# Motor_Interface_-_Pre-Charge_HV.net
KiCad netlist of a schematic drawn in Altium Designer
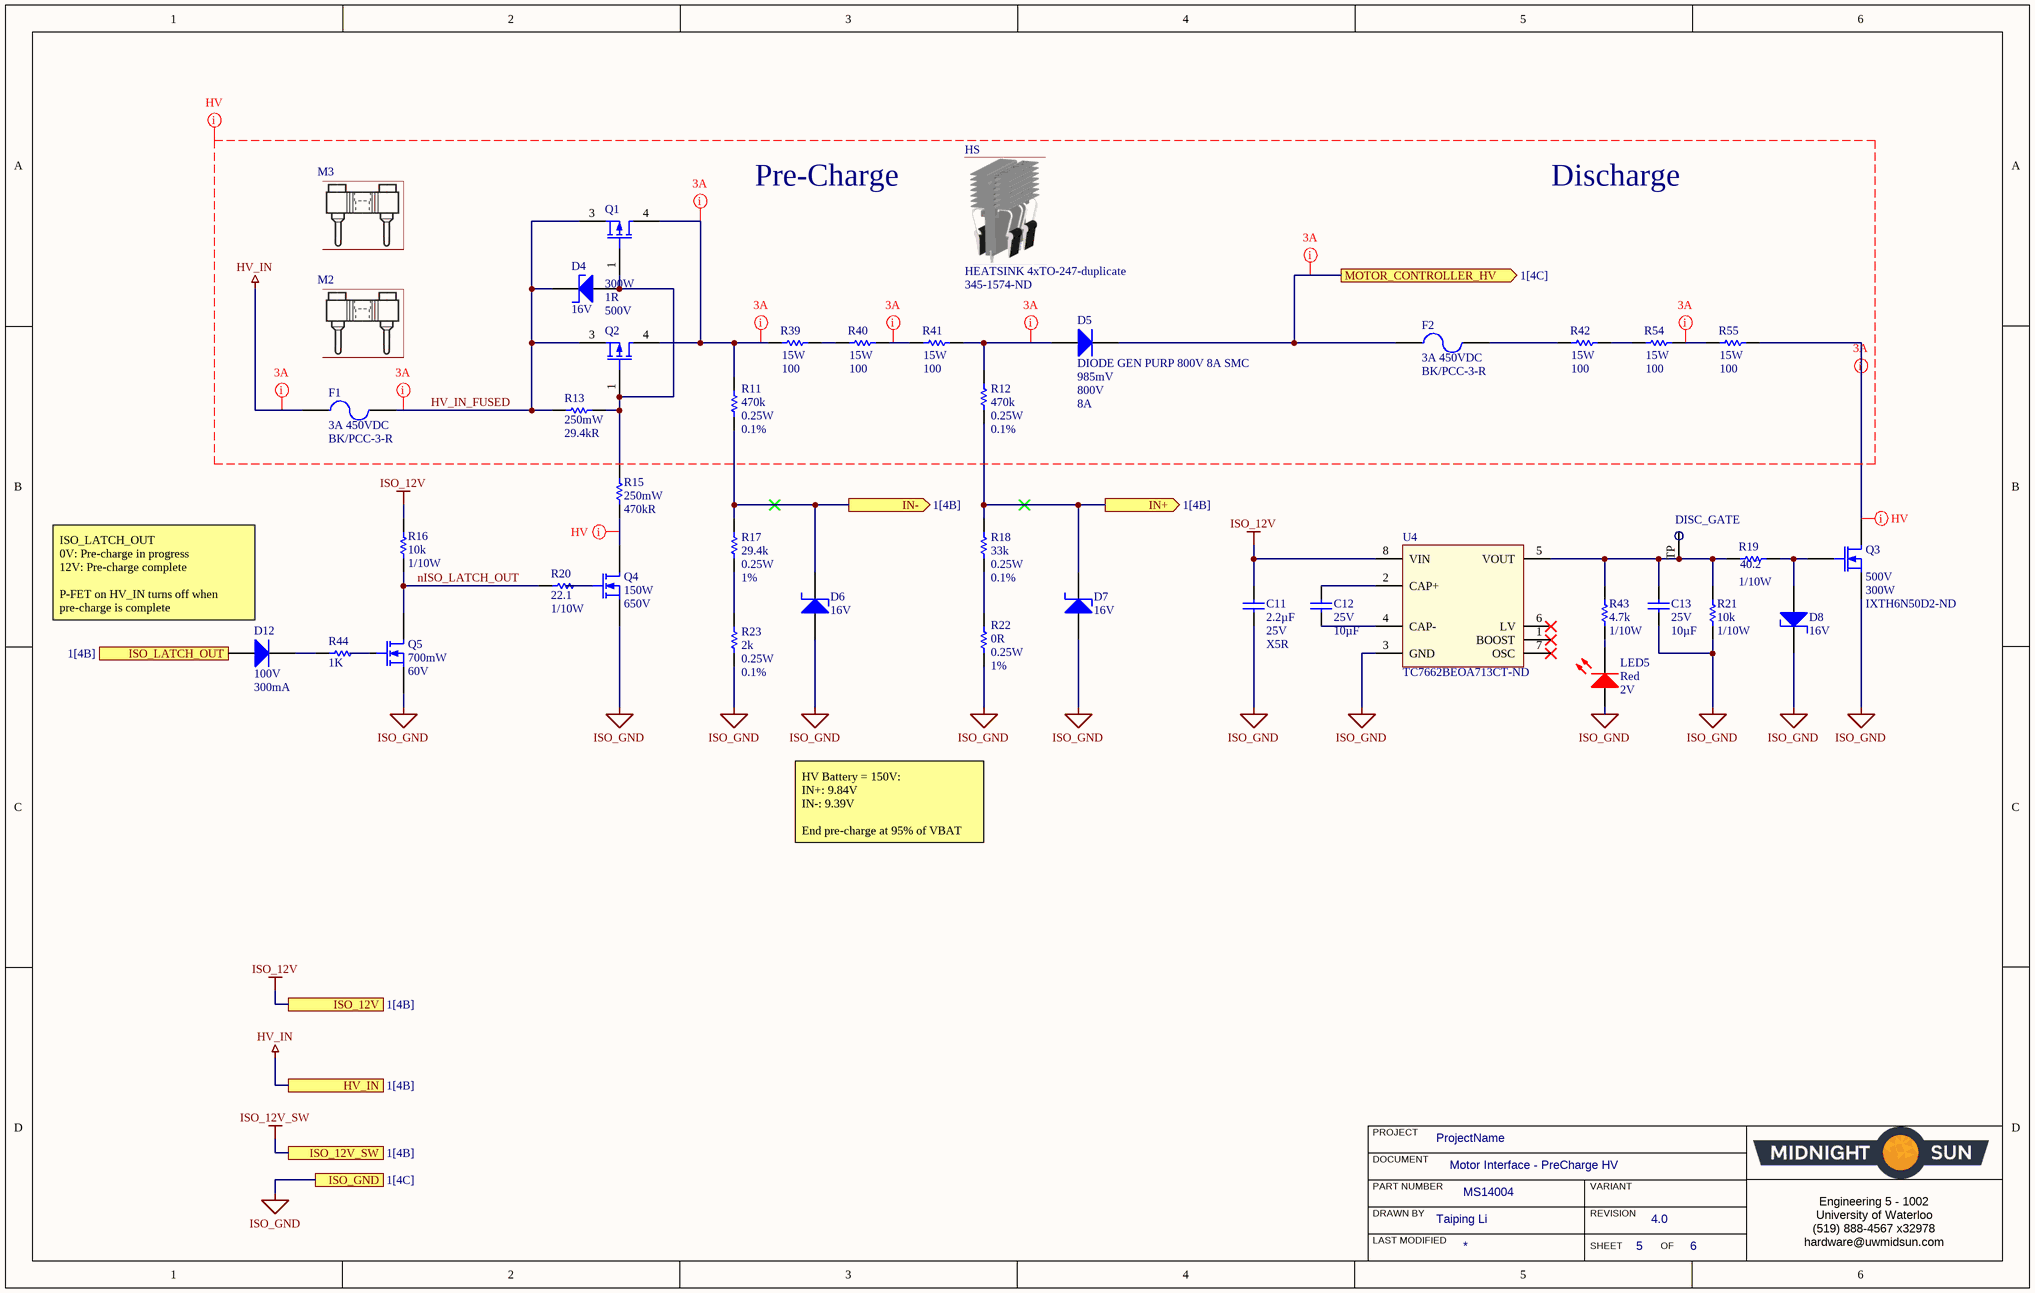
[diagram p0: Motor Interface - Pre-Charge HV.SchDoc]

(export (version "E")
  (design (tool "Eeschema 10.0.6"))
  (components
    (comp (ref "C11")
      (value "CAP CER 2.2UF 25V 10% X5R 0603")
      (footprint "CAP, 0603")
      (description "2.2µF ±10% 25V Ceramic Capacitor X5R 0603 (1608 Metric)")
      (fields
        (field (name "TOLERANCE") "±10%")
        (field (name "CAPACITANCE") "2.2µF")
        (field (name "VOLTAGE") "25V")
        (field (name "TEMPERATURE COEFFICIENT") "X5R")
      )
      (libsource (lib "Schematic Diagrams") (part "CAP CER 2.2UF 25V 10% X5R 0603"))
    )
    (comp (ref "C12")
      (value "CAP CER 10uF 25V 10% X5R 0805")
      (footprint "CAP, 0805")
      (description "10µF ±10% 25V Ceramic Capacitor X5R 0805 (2012 Metric)")
      (fields
        (field (name "MANUFACTURER") "Murata Electronics North America")
        (field (name "MANUFACTURER PART NUMBER") "GRM21BR61E106KA73L")
        (field (name "VOLTAGE - RATED") "25V")
        (field (name "CAPACITANCE") "10µF")
      )
      (libsource (lib "Schematic Diagrams") (part "CAP CER 10uF 25V 10% X5R 0805"))
    )
    (comp (ref "C13")
      (value "CAP CER 10uF 25V 10% X5R 0805")
      (footprint "CAP, 0805")
      (description "10µF ±10% 25V Ceramic Capacitor X5R 0805 (2012 Metric)")
      (fields
        (field (name "MANUFACTURER") "Murata Electronics North America")
        (field (name "MANUFACTURER PART NUMBER") "GRM21BR61E106KA73L")
        (field (name "VOLTAGE - RATED") "25V")
        (field (name "CAPACITANCE") "10µF")
      )
      (libsource (lib "Schematic Diagrams") (part "CAP CER 10uF 25V 10% X5R 0805"))
    )
    (comp (ref "D4")
      (value "DIODE ZENER 16V 5W DO-214AA (SMB)")
      (footprint "DO-214AA Diode")
      (description "Zener Diode 16V 5W ±5% Surface Mount DO-214AA (SMB)")
      (fields
        (field (name "MANUFACTURE PART NUMBER") "SMBJ5353B-TP")
        (field (name "VOLTAGE - ZENER (NOM)") "16V")
      )
      (libsource (lib "Schematic Diagrams") (part "DIODE ZENER 16V 5W DO-214AA (SMB)"))
    )
    (comp (ref "D5")
      (value "DIODE GEN PURP 800V 8A SMC")
      (footprint "DIODE, SMC")
      (fields
        (field (name "MANUFACTURER") "Diodes")
        (field (name "MANUFACTURER PART NUMBER") "S8KC-13")
        (field (name "FORWARD VOLTAGE") "985mV")
        (field (name "MAX REVERSE VOLTAGE (DC)") "800V")
        (field (name "FORWARD CURRENT") "8A")
      )
      (libsource (lib "Schematic Diagrams") (part "DIODE GEN PURP 800V 8A SMC"))
    )
    (comp (ref "D6")
      (value "DIODE ZENER 16V 5W DO-214AA (SMB)")
      (footprint "DO-214AA Diode")
      (description "Zener Diode 16V 5W ±5% Surface Mount DO-214AA (SMB)")
      (fields
        (field (name "MANUFACTURE PART NUMBER") "SMBJ5353B-TP")
        (field (name "VOLTAGE - ZENER (NOM)") "16V")
      )
      (libsource (lib "Schematic Diagrams") (part "DIODE ZENER 16V 5W DO-214AA (SMB)"))
    )
    (comp (ref "D7")
      (value "DIODE ZENER 16V 5W DO-214AA (SMB)")
      (footprint "DO-214AA Diode")
      (description "Zener Diode 16V 5W ±5% Surface Mount DO-214AA (SMB)")
      (fields
        (field (name "MANUFACTURE PART NUMBER") "SMBJ5353B-TP")
        (field (name "VOLTAGE - ZENER (NOM)") "16V")
      )
      (libsource (lib "Schematic Diagrams") (part "DIODE ZENER 16V 5W DO-214AA (SMB)"))
    )
    (comp (ref "D8")
      (value "DIODE ZENER 16V 5W DO-214AA (SMB)")
      (footprint "DO-214AA Diode")
      (description "Zener Diode 16V 5W ±5% Surface Mount DO-214AA (SMB)")
      (fields
        (field (name "MANUFACTURE PART NUMBER") "SMBJ5353B-TP")
        (field (name "VOLTAGE - ZENER (NOM)") "16V")
      )
      (libsource (lib "Schematic Diagrams") (part "DIODE ZENER 16V 5W DO-214AA (SMB)"))
    )
    (comp (ref "D12")
      (value "DIODE GEN PURP 100V 300MA SOD123")
      (footprint "DIODE GEN PURP 100V 300MA SOD123")
      (description "Diode Standard 100V 300mA (DC) Surface Mount SOD-123")
      (fields
        (field (name "MANUFACTURER") "Diodes Zetex")
        (field (name "MANUFACTURER PART NUMBER") "1N4148WQ-7-F")
        (field (name "MAX REPETITIVE REVERSE VOLTAGE (VRRM)") "100V")
        (field (name "FORWARD CURRENT") "300mA")
      )
      (libsource (lib "Schematic Diagrams") (part "DIODE GEN PURP 100V 300MA SOD123"))
    )
    (comp (ref "DISC_GATE")
      (value "Test Point")
      (footprint "Test Point")
      (libsource (lib "Schematic Diagrams") (part "Test Point"))
    )
    (comp (ref "F1")
      (value "3A 450VDC")
      (footprint "FUSE 5A 400VDC RADIAL")
      (description "FUSE BOARD MNT 3A 250VAC/450VDC")
      (fields (field (name "MANUFACTURER") "Eaton") (field (name "MANUFACTURER PART NUMBER") "BK/PCC-3-R"))
      (libsource (lib "Schematic Diagrams") (part "FUSE 3A 250VAC/450VDC RADIAL"))
    )
    (comp (ref "F2")
      (value "3A 450VDC")
      (footprint "FUSE 5A 400VDC RADIAL")
      (description "FUSE BOARD MNT 3A 250VAC/450VDC")
      (fields (field (name "MANUFACTURER") "Eaton") (field (name "MANUFACTURER PART NUMBER") "BK/PCC-3-R"))
      (libsource (lib "Schematic Diagrams") (part "FUSE 3A 250VAC/450VDC RADIAL"))
    )
    (comp (ref "HS")
      (value "HEATSINK 4xTO-247-duplicate")
      (footprint "HEATSINK 4x TO-247 - duplicate")
      (description "n Heat Sink TO-220, TO-247, TO-264 Aluminum Board Level, Vertical")
      (fields
        (field (name "MANUFACTURER") "Wakefield")
        (field (name "MANUFACTURER PART NUMBER") "OMNI-UNI-30-50-D")
        (field (name "SUPPLIER PART NUMBER 1") "345-1574-ND")
      )
      (libsource (lib "Schematic Diagrams") (part "HEATSINK 4xTO-247-duplicate"))
    )
    (comp (ref "LED5")
      (value "LED RED CLEAR 2V 0603")
      (footprint "LED_0603")
      (description "Red 631nm LED Indication - Discrete 2V 0603 (1608 Metric)")
      (fields
        (field (name "MANUFACTURER") "Wurth Electronics Inc.")
        (field (name "MANUFACTURER PART NUMBER") "150060RS75000")
        (field (name "COLOR") "Red")
        (field (name "VOLTAGE - FORWARD (VF) (TYP)") "2V")
      )
      (libsource (lib "Schematic Diagrams") (part "LED RED CLEAR 2V 0603"))
    )
    (comp (ref "M2")
      (value "FUSE HOLDER PC-TRON RADIAL")
      (description "Fuse Holder 1 Circuit Radial PCB")
      (fields (field (name "MANUFACTURER") "Eaton") (field (name "MANUFACTURER PART NUMBER") "BK/PCS"))
      (libsource (lib "Schematic Diagrams") (part "FUSE HOLDER PC-TRON RADIAL"))
    )
    (comp (ref "M3")
      (value "FUSE HOLDER PC-TRON RADIAL")
      (description "Fuse Holder 1 Circuit Radial PCB")
      (fields (field (name "MANUFACTURER") "Eaton") (field (name "MANUFACTURER PART NUMBER") "BK/PCS"))
      (libsource (lib "Schematic Diagrams") (part "FUSE HOLDER PC-TRON RADIAL"))
    )
    (comp (ref "Q1")
      (value "IXTA10P50P")
      (footprint "P-CH MOSFET 500V 10A 300W TO-263")
      (description "P-Channel 500V 10A (Tc) 300W (Tc) Surface Mount TO-263 (IXTA)")
      (fields
        (field (name "MANUFACTURER") "IXYS")
        (field (name "MAX POWER DISSIPATION") "300W")
        (field (name "RDS ON MAX") "1R")
        (field (name "DRAIN TO SOURCE VOLTAGE (VDSS)") "500V")
      )
      (libsource (lib "Schematic Diagrams") (part "MOSFET P-CH 500V 10A 300W TO-263"))
    )
    (comp (ref "Q2")
      (value "IXTA10P50P")
      (footprint "P-CH MOSFET 500V 10A 300W TO-263")
      (description "P-Channel 500V 10A (Tc) 300W (Tc) Surface Mount TO-263 (IXTA)")
      (fields (field (name "MANUFACTURER") "IXYS"))
      (libsource (lib "Schematic Diagrams") (part "MOSFET P-CH 500V 10A 300W TO-263"))
    )
    (comp (ref "Q3")
      (value "MOSFET DEPLETION N-CH 500V 6A TO247")
      (footprint "N-CH Depletion Mode TO-247-3")
      (description "N-Channel 500V 6A (Tc) 300W (Tc) Through Hole TO-247 (IXTH)")
      (fields
        (field (name "MANUFACTURER") "IXYS")
        (field (name "MANUFACTURER PART NUMBER") "IXTH6N50D2")
        (field (name "DRAIN TO SOURCE VOLTAGE (VDSS)") "500V")
        (field (name "MAX POWER DISSIPATION") "300W")
        (field (name "SUPPLIER PART NUMBER 1") "IXTH6N50D2-ND")
      )
      (libsource (lib "Schematic Diagrams") (part "MOSFET DEPLETION N-CH 500V 6A TO247"))
    )
    (comp (ref "Q4")
      (value "MOSFET N-CH 650V 8A X2 TO-263")
      (footprint "P-CH MOSFET 500V 10A 300W TO-263")
      (description "N-Channel 650V 8A (Tc) 150W (Tc) Surface Mount TO-263")
      (fields
        (field (name "MANUFACTURER") "IXYS")
        (field (name "MAX POWER DISSIPATION") "150W")
        (field (name "DRAIN TO SOURCE VOLTAGE (VDSS)") "650V")
        (field (name "MANUFACTURER PART NUMBER") "IXTA8N65X2")
      )
      (libsource (lib "Schematic Diagrams") (part "MOSFET N-CH 650V 8A X2 TO-263"))
    )
    (comp (ref "Q5")
      (value "MOSFET N-CH 60V 310MA SOT23")
      (footprint "SOT23")
      (description "N-Channel 60V 310mA (Ta) 370mW (Ta) Surface Mount SOT-23")
      (fields
        (field (name "MANUFACTURER") "Diodes")
        (field (name "MANUFACTURER PART NUMBER") "DMN6140L-7")
        (field (name "MAX POWER DISSIPATION") "700mW")
        (field (name "DRAIN TO SOURCE VOLTAGE (VDSS)") "60V")
      )
      (libsource (lib "Schematic Diagrams") (part "MOSFET N-CH 60V 310MA SOT23"))
    )
    (comp (ref "R11")
      (value "RESISTOR")
      (footprint "RES 1206")
      (fields
        (field (name "MANUFACTURER") "Susumu")
        (field (name "MANUFACTURER PART NUMBER") "RG3216P-4703-B-T1")
        (field (name "TOLERANCE") "0.1%")
        (field (name "MAX POWER DISSIPATION") "0.25W")
        (field (name "RESISTANCE") "470k")
      )
      (libsource (lib "Schematic Diagrams") (part "RES SMD 470K OHM 0.1% 1/4W 1206"))
    )
    (comp (ref "R12")
      (value "RESISTOR")
      (footprint "RES 1206")
      (fields
        (field (name "MANUFACTURER") "Susumu")
        (field (name "MANUFACTURER PART NUMBER") "RG3216P-4703-B-T1")
        (field (name "TOLERANCE") "0.1%")
        (field (name "MAX POWER DISSIPATION") "0.25W")
        (field (name "RESISTANCE") "470k")
      )
      (libsource (lib "Schematic Diagrams") (part "RES SMD 470K OHM 0.1% 1/4W 1206"))
    )
    (comp (ref "R13")
      (value "Resistor")
      (footprint "RES 1206")
      (description "29.4 kOhms ±1% 0.25W, 1/4W Chip Resistor 1206 (3216 Metric) Automotive AEC-Q200 Thick Film")
      (fields
        (field (name "MANUFACTURER") "Panasonic")
        (field (name "MANUFACTURER PART NUMBER") "ERJ-8ENF2942V")
        (field (name "MAX POWER DISSIPATION") "250mW")
        (field (name "RESISTANCE") "29.4kR")
      )
      (libsource (lib "Schematic Diagrams") (part "RES SMD 29.4K OHM 1% 1/4W 1206"))
    )
    (comp (ref "R15")
      (value "RESISTOR")
      (footprint "RES 1206")
      (fields
        (field (name "MANUFACTURER") "Susumu")
        (field (name "MANUFACTURER PART NUMBER") "RG3216P-4703-B-T1")
        (field (name "TOLERANCE") "0.1%")
        (field (name "MAX POWER DISSIPATION") "250mW")
        (field (name "RESISTANCE") "470kR")
      )
      (libsource (lib "Schematic Diagrams") (part "RES SMD 470K OHM 0.1% 1/4W 1206"))
    )
    (comp (ref "R16")
      (value "RES 10K OHM 1% 1/10W 0603")
      (footprint "RES, 0603")
      (description "RES SMD 10K OHM 1% 1/10W 0603")
      (fields
        (field (name "TOLERANCE") "±1%")
        (field (name "RESISTANCE") "10k")
        (field (name "POWER") "1/10W")
      )
      (libsource (lib "Schematic Diagrams") (part "RES 10K OHM 1% 1/10W 0603"))
    )
    (comp (ref "R17")
      (value "Resistor")
      (footprint "RES 1206")
      (description "29.4 kOhms ±1% 0.25W, 1/4W Chip Resistor 1206 (3216 Metric) Automotive AEC-Q200 Thick Film")
      (fields
        (field (name "MANUFACTURER") "Panasonic")
        (field (name "MANUFACTURER PART NUMBER") "ERJ-8ENF2942V")
        (field (name "TOLERANCE") "1%")
        (field (name "MAX POWER DISSIPATION") "0.25W")
        (field (name "RESISTANCE") "29.4k")
      )
      (libsource (lib "Schematic Diagrams") (part "RES SMD 29.4K OHM 1% 1/4W 1206"))
    )
    (comp (ref "R18")
      (value "Resistor")
      (footprint "RES 1206")
      (description "33 kOhms ±0.1% 0.25W, 1/4W Chip Resistor 1206 (3216 Metric) Thin Film")
      (fields
        (field (name "MANUFACTURER") "Yageo")
        (field (name "MANUFACTURER PART NUMBER") "RT1206BRD0733KL")
        (field (name "TOLERANCE") "0.1%")
        (field (name "RESISTANCE") "33k")
        (field (name "MAX POWER DISSIPATION") "0.25W")
      )
      (libsource (lib "Schematic Diagrams") (part "RES SMD 33K OHM 0.1% 1/4W 1206"))
    )
    (comp (ref "R19")
      (value "RES 40.2 OHM 0.5% 1/10W 0603")
      (footprint "RES, 0603")
      (description "RES SMD 40.2 OHM 0.5% 1/10W 0603")
      (fields
        (field (name "TOLERANCE") "±0.5%")
        (field (name "RESISTANCE") "40.2")
        (field (name "POWER") "1/10W")
      )
      (libsource (lib "Schematic Diagrams") (part "RES 40.2 OHM 0.5% 1/10W 0603"))
    )
    (comp (ref "R20")
      (value "RES 22.1 OHM 1% 1/10W 0603")
      (footprint "RES, 0603")
      (description "22.1 Ohm ±1% 0.1W, 1/10W Chip Resistor 0603 (1608 Metric) Moisture Resistant Thick Film")
      (fields
        (field (name "TOLERANCE") "±1%")
        (field (name "RESISTANCE") "22.1")
        (field (name "POWER") "1/10W")
      )
      (libsource (lib "Schematic Diagrams") (part "RES 22.1 OHM 1% 1/10W 0603"))
    )
    (comp (ref "R21")
      (value "RES 10K OHM 1% 1/10W 0603")
      (footprint "RES, 0603")
      (description "RES SMD 10K OHM 1% 1/10W 0603")
      (fields
        (field (name "TOLERANCE") "±1%")
        (field (name "RESISTANCE") "10k")
        (field (name "POWER") "1/10W")
      )
      (libsource (lib "Schematic Diagrams") (part "RES 10K OHM 1% 1/10W 0603"))
    )
    (comp (ref "R22")
      (value "RES SMD 0 OHM JUMPER 1/4W 1206")
      (footprint "RES 1206")
      (description "0 Ohms Jumper 0.25W, 1/4W Chip Resistor 1206 (3216 Metric) Automotive AEC-Q200 Thick Film")
      (fields
        (field (name "MANUFACTURER") "Vishay")
        (field (name "MANUFACTURER PART NUMBER") "CRCW12060000Z0EA")
        (field (name "TOLERANCE") "1%")
        (field (name "POWER RATING") "0.25W")
        (field (name "RESISTANCE") "0R")
      )
      (libsource (lib "Schematic Diagrams") (part "RES SMD 0 OHM JUMPER 1/4W 1206"))
    )
    (comp (ref "R23")
      (value "RES SMD 2K OHM 0.1% 1/4W 1206")
      (footprint "RES 1206")
      (description "2 kOhms ±0.1% 0.25W, 1/4W Chip Resistor 1206 (3216 Metric) Automotive AEC-Q200 Thin Film")
      (fields
        (field (name "MANUFACTURER") "Panasonic")
        (field (name "MANUFACTURER PART NUMBER") "ERA-8AEB202V")
        (field (name "TOLERANCE") "0.1%")
        (field (name "MAX POWER DISSIPATION") "0.25W")
        (field (name "RESISTANCE") "2k")
      )
      (libsource (lib "Schematic Diagrams") (part "RES SMD 2K OHM 0.1% 1/4W 1206"))
    )
    (comp (ref "R39")
      (value "RES 100 OHM 15W 1% TO126")
      (footprint "RES TO-126-2")
      (description "100 Ohms ±1% 15W Through Hole Resistor TO-126-2 Moisture Resistant, Non-Inductive Thick Film")
      (fields (field (name "TOLERANCE") "1%"))
      (libsource (lib "Schematic Diagrams") (part "RES 100 OHM 15W 1% TO126"))
    )
    (comp (ref "R40")
      (value "RES 100 OHM 15W 1% TO126")
      (footprint "RES TO-126-2")
      (description "100 Ohms ±1% 15W Through Hole Resistor TO-126-2 Moisture Resistant, Non-Inductive Thick Film")
      (fields (field (name "TOLERANCE") "1%"))
      (libsource (lib "Schematic Diagrams") (part "RES 100 OHM 15W 1% TO126"))
    )
    (comp (ref "R41")
      (value "RES 100 OHM 15W 1% TO126")
      (footprint "RES TO-126-2")
      (description "100 Ohms ±1% 15W Through Hole Resistor TO-126-2 Moisture Resistant, Non-Inductive Thick Film")
      (fields (field (name "TOLERANCE") "1%"))
      (libsource (lib "Schematic Diagrams") (part "RES 100 OHM 15W 1% TO126"))
    )
    (comp (ref "R42")
      (value "RES 100 OHM 15W 1% TO126")
      (footprint "RES TO-126-2")
      (description "100 Ohms ±1% 15W Through Hole Resistor TO-126-2 Moisture Resistant, Non-Inductive Thick Film")
      (fields (field (name "TOLERANCE") "1%"))
      (libsource (lib "Schematic Diagrams") (part "RES 100 OHM 15W 1% TO126"))
    )
    (comp (ref "R43")
      (value "RES 4.7K OHM 1% 1/10W 0603")
      (footprint "RES, 0603")
      (description "4.7k Ohm ±1% 0.1W, 1/10W Chip Resistor 0603 (1608 Metric) Moisture Resistant Thick Film")
      (fields
        (field (name "TOLERANCE") "±1%")
        (field (name "RESISTANCE (OHMS)") "4.7k")
        (field (name "POWER (WATTS)") "1/10W")
      )
      (libsource (lib "Schematic Diagrams") (part "RES 4.7K OHM 1% 1/10W 0603"))
    )
    (comp (ref "R44")
      (value "1K")
      (footprint "RES, 0603")
      (description "1k Ohm ±5% 0.1W, 1/10W Chip Resistor 0603 (1608 Metric)")
      (fields
        (field (name "MANUFACTURER") "Yageo")
        (field (name "MANUFACTURER PART NUMBER") "RC0603JR-071KL")
      )
      (libsource (lib "Schematic Diagrams") (part "RES 1K OHM 5% 1/10W 0603"))
    )
    (comp (ref "R54")
      (value "RES 100 OHM 15W 1% TO126")
      (footprint "RES TO-126-2")
      (description "100 Ohms ±1% 15W Through Hole Resistor TO-126-2 Moisture Resistant, Non-Inductive Thick Film")
      (fields (field (name "TOLERANCE") "1%"))
      (libsource (lib "Schematic Diagrams") (part "RES 100 OHM 15W 1% TO126"))
    )
    (comp (ref "R55")
      (value "RES 100 OHM 15W 1% TO126")
      (footprint "RES TO-126-2")
      (description "100 Ohms ±1% 15W Through Hole Resistor TO-126-2 Moisture Resistant, Non-Inductive Thick Film")
      (fields (field (name "TOLERANCE") "1%"))
      (libsource (lib "Schematic Diagrams") (part "RES 100 OHM 15W 1% TO126"))
    )
    (comp (ref "U4")
      (value "IC REG SWTCHD CAP INV 20MA 8SOIC")
      (footprint "SOIC8")
      (fields
        (field (name "MANUFACTURER") "Microchip")
        (field (name "MANUFACTURER PART NUMBER") "TC7662BEOA713")
        (field (name "SUPPLIER PART NUMBER 1") "TC7662BEOA713CT-ND")
      )
      (libsource (lib "Schematic Diagrams") (part "IC REG SWTCHD CAP INV 20MA 8SOIC"))
    )
  )
  (nets
    (net (code "1") (name "/HV_IN_FUSED") (class "Default")
      (node (ref "D4") (pin "2") (pinfunction "K_2") (pintype "passive"))
      (node (ref "F1") (pin "2") (pinfunction "2_2") (pintype "passive"))
      (node (ref "Q1") (pin "3") (pinfunction "S_3") (pintype "passive"))
      (node (ref "Q2") (pin "3") (pinfunction "S_3") (pintype "passive"))
      (node (ref "R13") (pin "1") (pinfunction "1_1") (pintype "passive"))
    )
    (net (code "2") (name "/IN+") (class "Default")
      (node (ref "D7") (pin "2") (pinfunction "K_2") (pintype "passive"))
      (node (ref "R12") (pin "2") (pinfunction "2_2") (pintype "passive"))
      (node (ref "R18") (pin "1") (pinfunction "1_1") (pintype "passive"))
    )
    (net (code "3") (name "/IN-") (class "Default")
      (node (ref "D6") (pin "2") (pinfunction "K_2") (pintype "passive"))
      (node (ref "R11") (pin "2") (pinfunction "2_2") (pintype "passive"))
      (node (ref "R17") (pin "1") (pinfunction "1_1") (pintype "passive"))
    )
    (net (code "4") (name "/ISO_LATCH_OUT") (class "Default")
      (node (ref "D12") (pin "1") (pinfunction "A_1") (pintype "passive"))
    )
    (net (code "5") (name "/MOTOR_CONTROLLER_HV") (class "Default")
      (node (ref "D5") (pin "1") (pinfunction "K_1") (pintype "passive"))
      (node (ref "F2") (pin "1") (pinfunction "1_1") (pintype "passive"))
    )
    (net (code "6") (name "/nISO_LATCH_OUT") (class "Default")
      (node (ref "Q5") (pin "1") (pinfunction "D_1") (pintype "passive"))
      (node (ref "R16") (pin "2") (pinfunction "2_2") (pintype "passive"))
      (node (ref "R20") (pin "1") (pinfunction "1_1") (pintype "passive"))
    )
    (net (code "7") (name "HV_IN") (class "Default")
      (node (ref "F1") (pin "1") (pinfunction "1_1") (pintype "passive"))
    )
    (net (code "8") (name "ISO_12V") (class "Default")
      (node (ref "C11") (pin "2") (pinfunction "2_2") (pintype "passive"))
      (node (ref "R16") (pin "1") (pinfunction "1_1") (pintype "passive"))
      (node (ref "U4") (pin "8") (pinfunction "VIN_8") (pintype "power_in"))
    )
    (net (code "10") (name "ISO_GND") (class "Default")
      (node (ref "C11") (pin "1") (pinfunction "1_1") (pintype "passive"))
      (node (ref "C13") (pin "2") (pinfunction "2_2") (pintype "passive"))
      (node (ref "D6") (pin "1") (pinfunction "A_1") (pintype "passive"))
      (node (ref "D7") (pin "1") (pinfunction "A_1") (pintype "passive"))
      (node (ref "D8") (pin "2") (pinfunction "K_2") (pintype "passive"))
      (node (ref "LED5") (pin "1") (pinfunction "A_1") (pintype "passive"))
      (node (ref "Q3") (pin "3") (pinfunction "S_3") (pintype "passive"))
      (node (ref "Q4") (pin "3") (pinfunction "S_3") (pintype "passive"))
      (node (ref "Q5") (pin "2") (pinfunction "S_2") (pintype "passive"))
      (node (ref "R21") (pin "2") (pinfunction "2_2") (pintype "passive"))
      (node (ref "R22") (pin "2") (pinfunction "2_2") (pintype "passive"))
      (node (ref "R23") (pin "2") (pinfunction "2_2") (pintype "passive"))
      (node (ref "U4") (pin "3") (pinfunction "GND_3") (pintype "power_in"))
    )
    (net (code "11") (name "Net-(D4-A)") (class "Default")
      (node (ref "D4") (pin "1") (pinfunction "A_1") (pintype "passive"))
      (node (ref "Q1") (pin "1") (pinfunction "G_1") (pintype "passive"))
      (node (ref "Q2") (pin "1") (pinfunction "G_1") (pintype "passive"))
      (node (ref "R13") (pin "2") (pinfunction "2_2") (pintype "passive"))
      (node (ref "R15") (pin "1") (pinfunction "1_1") (pintype "passive"))
    )
    (net (code "12") (name "Net-(D5-A)") (class "Default")
      (node (ref "D5") (pin "2") (pinfunction "A_2") (pintype "passive"))
      (node (ref "R12") (pin "1") (pinfunction "1_1") (pintype "passive"))
      (node (ref "R41") (pin "2") (pinfunction "2_2") (pintype "passive"))
    )
    (net (code "13") (name "Net-(D8-A)") (class "Default")
      (node (ref "D8") (pin "1") (pinfunction "A_1") (pintype "passive"))
      (node (ref "Q3") (pin "1") (pinfunction "G_1") (pintype "passive"))
      (node (ref "R19") (pin "2") (pinfunction "2_2") (pintype "passive"))
    )
    (net (code "14") (name "Net-(D12-K)") (class "Default")
      (node (ref "D12") (pin "2") (pinfunction "K_2") (pintype "passive"))
      (node (ref "R44") (pin "1") (pinfunction "1_1") (pintype "passive"))
    )
    (net (code "15") (name "Net-(DISC_GATE-1)") (class "Default")
      (node (ref "C13") (pin "1") (pinfunction "1_1") (pintype "passive"))
      (node (ref "DISC_GATE") (pin "TP") (pinfunction "1_TP") (pintype "passive"))
      (node (ref "R19") (pin "1") (pinfunction "1_1") (pintype "passive"))
      (node (ref "R21") (pin "1") (pinfunction "1_1") (pintype "passive"))
      (node (ref "R43") (pin "1") (pinfunction "1_1") (pintype "passive"))
      (node (ref "U4") (pin "5") (pinfunction "VOUT_5") (pintype "power_in"))
    )
    (net (code "16") (name "Net-(F2-Pad2)") (class "Default")
      (node (ref "F2") (pin "2") (pinfunction "2_2") (pintype "passive"))
      (node (ref "R42") (pin "1") (pinfunction "1_1") (pintype "passive"))
    )
    (net (code "17") (name "Net-(LED5-K)") (class "Default")
      (node (ref "LED5") (pin "2") (pinfunction "K_2") (pintype "passive"))
      (node (ref "R43") (pin "2") (pinfunction "2_2") (pintype "passive"))
    )
    (net (code "18") (name "Net-(Q1-D)") (class "Default")
      (node (ref "Q1") (pin "4") (pinfunction "D_4") (pintype "passive"))
      (node (ref "Q2") (pin "4") (pinfunction "D_4") (pintype "passive"))
      (node (ref "R11") (pin "1") (pinfunction "1_1") (pintype "passive"))
      (node (ref "R39") (pin "1") (pinfunction "1_1") (pintype "passive"))
    )
    (net (code "19") (name "Net-(Q3-D)") (class "Default")
      (node (ref "Q3") (pin "2") (pinfunction "D_2") (pintype "passive"))
      (node (ref "R55") (pin "2") (pinfunction "2_2") (pintype "passive"))
    )
    (net (code "20") (name "Net-(Q4-D)") (class "Default")
      (node (ref "Q4") (pin "4") (pinfunction "D_4") (pintype "passive"))
      (node (ref "R15") (pin "2") (pinfunction "2_2") (pintype "passive"))
    )
    (net (code "21") (name "Net-(Q4-G)") (class "Default")
      (node (ref "Q4") (pin "1") (pinfunction "G_1") (pintype "passive"))
      (node (ref "R20") (pin "2") (pinfunction "2_2") (pintype "passive"))
    )
    (net (code "22") (name "Net-(Q5-G)") (class "Default")
      (node (ref "Q5") (pin "3") (pinfunction "G_3") (pintype "passive"))
      (node (ref "R44") (pin "2") (pinfunction "2_2") (pintype "passive"))
    )
    (net (code "23") (name "Net-(R17-Pad2)") (class "Default")
      (node (ref "R17") (pin "2") (pinfunction "2_2") (pintype "passive"))
      (node (ref "R23") (pin "1") (pinfunction "1_1") (pintype "passive"))
    )
    (net (code "24") (name "Net-(R18-Pad2)") (class "Default")
      (node (ref "R18") (pin "2") (pinfunction "2_2") (pintype "passive"))
      (node (ref "R22") (pin "1") (pinfunction "1_1") (pintype "passive"))
    )
    (net (code "25") (name "Net-(R39-Pad2)") (class "Default")
      (node (ref "R39") (pin "2") (pinfunction "2_2") (pintype "passive"))
      (node (ref "R40") (pin "1") (pinfunction "1_1") (pintype "passive"))
    )
    (net (code "26") (name "Net-(R40-Pad2)") (class "Default")
      (node (ref "R40") (pin "2") (pinfunction "2_2") (pintype "passive"))
      (node (ref "R41") (pin "1") (pinfunction "1_1") (pintype "passive"))
    )
    (net (code "27") (name "Net-(R42-Pad2)") (class "Default")
      (node (ref "R42") (pin "2") (pinfunction "2_2") (pintype "passive"))
      (node (ref "R54") (pin "1") (pinfunction "1_1") (pintype "passive"))
    )
    (net (code "28") (name "Net-(R54-Pad2)") (class "Default")
      (node (ref "R54") (pin "2") (pinfunction "2_2") (pintype "passive"))
      (node (ref "R55") (pin "1") (pinfunction "1_1") (pintype "passive"))
    )
    (net (code "29") (name "Net-(U4-CAP+)") (class "Default")
      (node (ref "C12") (pin "1") (pinfunction "1_1") (pintype "passive"))
      (node (ref "U4") (pin "2") (pinfunction "CAP+_2") (pintype "passive"))
    )
    (net (code "30") (name "Net-(U4-CAP-)") (class "Default")
      (node (ref "C12") (pin "2") (pinfunction "2_2") (pintype "passive"))
      (node (ref "U4") (pin "4") (pinfunction "CAP-_4") (pintype "power_in"))
    )
    (net (code "31") (name "unconnected-(U4-BOOST-Pad1)") (class "Default")
      (node (ref "U4") (pin "1") (pinfunction "BOOST_1") (pintype "power_in+no_connect"))
    )
    (net (code "32") (name "unconnected-(U4-LV-Pad6)") (class "Default")
      (node (ref "U4") (pin "6") (pinfunction "LV_6") (pintype "power_in+no_connect"))
    )
    (net (code "33") (name "unconnected-(U4-OSC-Pad7)") (class "Default")
      (node (ref "U4") (pin "7") (pinfunction "OSC_7") (pintype "power_in+no_connect"))
    )
  )
)
